# rb1_2_panelized.net
KiCad netlist of a schematic drawn in EAGLE
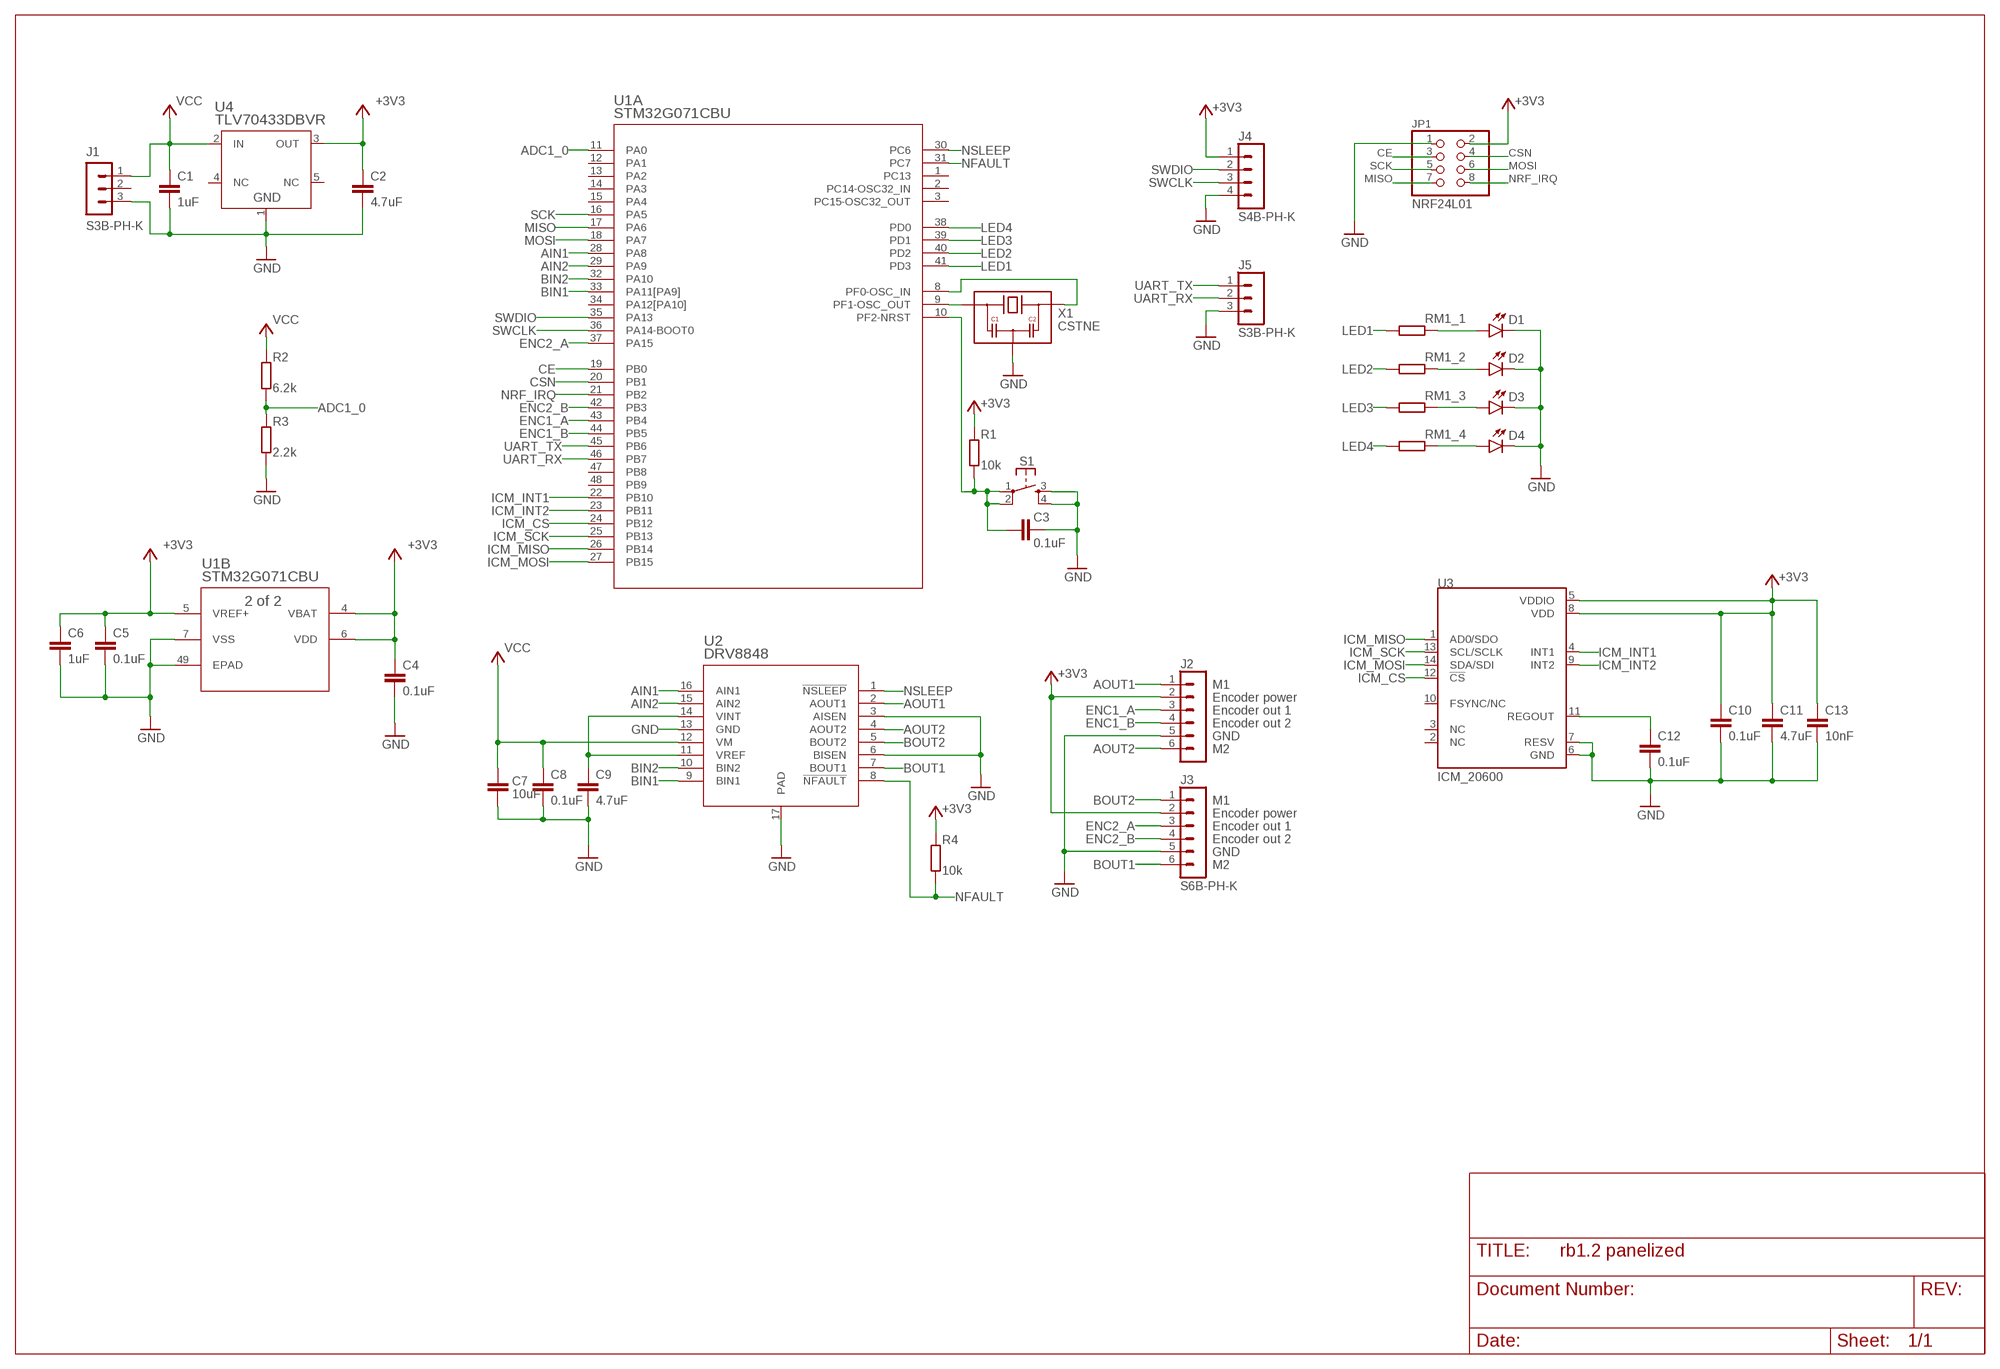
[diagram p0: schematic, sheet 1]

(export (version "E")
  (design (tool "Eeschema 10.0.6"))
  (components
    (comp (ref "C1")
      (value "1uF")
      (footprint "eagle-import:C0603K")
      (libsource (lib "eagle-import") (part "C-EU-K0603"))
    )
    (comp (ref "C2")
      (value "4.7uF")
      (footprint "eagle-import:C0603K")
      (libsource (lib "eagle-import") (part "C-EU-K0603"))
    )
    (comp (ref "C3")
      (value "0.1uF")
      (footprint "eagle-import:C0402K")
      (libsource (lib "eagle-import") (part "C-EU-K0402"))
    )
    (comp (ref "C4")
      (value "0.1uF")
      (footprint "eagle-import:C0603K")
      (libsource (lib "eagle-import") (part "C-EU-K0603"))
    )
    (comp (ref "C5")
      (value "0.1uF")
      (footprint "eagle-import:C0603K")
      (libsource (lib "eagle-import") (part "C-EU-K0603"))
    )
    (comp (ref "C6")
      (value "1uF")
      (footprint "eagle-import:C0603K")
      (libsource (lib "eagle-import") (part "C-EU-K0603"))
    )
    (comp (ref "C7")
      (value "10uF")
      (footprint "eagle-import:C1206K")
      (libsource (lib "eagle-import") (part "C-EU-K1206"))
    )
    (comp (ref "C8")
      (value "0.1uF")
      (footprint "eagle-import:C0603K")
      (libsource (lib "eagle-import") (part "C-EU-K0603"))
    )
    (comp (ref "C9")
      (value "4.7uF")
      (footprint "eagle-import:C0603K")
      (libsource (lib "eagle-import") (part "C-EU-K0603"))
    )
    (comp (ref "C10")
      (value "0.1uF")
      (footprint "eagle-import:C0603K")
      (libsource (lib "eagle-import") (part "C-EU-K0603"))
    )
    (comp (ref "C11")
      (value "4.7uF")
      (footprint "eagle-import:C0603K")
      (libsource (lib "eagle-import") (part "C-EU-K0603"))
    )
    (comp (ref "C12")
      (value "0.1uF")
      (footprint "eagle-import:C0603K")
      (libsource (lib "eagle-import") (part "C-EU-K0603"))
    )
    (comp (ref "C13")
      (value "10nF")
      (footprint "eagle-import:C0603K")
      (libsource (lib "eagle-import") (part "C-EU-K0603"))
    )
    (comp (ref "D1")
      (value "LED0805")
      (footprint "eagle-import:LED-0805")
      (libsource (lib "eagle-import") (part "LED0805"))
    )
    (comp (ref "D2")
      (value "LED0805")
      (footprint "eagle-import:LED-0805")
      (libsource (lib "eagle-import") (part "LED0805"))
    )
    (comp (ref "D3")
      (value "LED0805")
      (footprint "eagle-import:LED-0805")
      (libsource (lib "eagle-import") (part "LED0805"))
    )
    (comp (ref "D4")
      (value "LED0805")
      (footprint "eagle-import:LED-0805")
      (libsource (lib "eagle-import") (part "LED0805"))
    )
    (comp (ref "J1")
      (value "S3B-PH-K")
      (footprint "eagle-import:S3B-PH-K")
      (libsource (lib "eagle-import") (part "S3B-PH-K"))
    )
    (comp (ref "J2")
      (value "S6B-PH-K")
      (footprint "eagle-import:S6B-PH-K")
      (libsource (lib "eagle-import") (part "S6B-PH-K"))
    )
    (comp (ref "J3")
      (value "S6B-PH-K")
      (footprint "eagle-import:S6B-PH-K")
      (libsource (lib "eagle-import") (part "S6B-PH-K"))
    )
    (comp (ref "J4")
      (value "S4B-PH-K")
      (footprint "eagle-import:S4B-PH-K")
      (libsource (lib "eagle-import") (part "S4B-PH-K"))
    )
    (comp (ref "J5")
      (value "S3B-PH-K")
      (footprint "eagle-import:S3B-PH-K")
      (libsource (lib "eagle-import") (part "S3B-PH-K"))
    )
    (comp (ref "JP1")
      (value "NRF24L01")
      (footprint "eagle-import:2X04")
      (libsource (lib "eagle-import") (part "PINHD-2X4"))
    )
    (comp (ref "R1")
      (value "10k")
      (footprint "eagle-import:R0603")
      (libsource (lib "eagle-import") (part "R-EU0603"))
    )
    (comp (ref "R2")
      (value "6.2k")
      (footprint "eagle-import:R0603")
      (libsource (lib "eagle-import") (part "R-EU0603"))
    )
    (comp (ref "R3")
      (value "2.2k")
      (footprint "eagle-import:R0603")
      (libsource (lib "eagle-import") (part "R-EU0603"))
    )
    (comp (ref "R4")
      (value "10k")
      (footprint "eagle-import:R0603")
      (libsource (lib "eagle-import") (part "R-EU0603"))
    )
    (comp (ref "RM1")
      (value "RES_ARRAY")
      (footprint "eagle-import:0603-ARC")
      (libsource (lib "eagle-import") (part "RES_ARRAY"))
    )
    (comp (ref "S1")
      (value "MOMENTARY-SWITCH-SPST-2-[SMD-5.2MM]")
      (footprint "eagle-import:TACTILE_SWITCH_SMD_5.2MM")
      (libsource (lib "eagle-import") (part "MOMENTARY-SWITCH-SPST-2-[SMD-5.2MM]"))
    )
    (comp (ref "U1")
      (value "STM32G071CBU")
      (footprint "eagle-import:UFQFPN48-7X7MM")
      (libsource (lib "eagle-import") (part "STM32G0_UFQFPN48"))
    )
    (comp (ref "U2")
      (value "DRV8848")
      (footprint "eagle-import:HTSSOP")
      (libsource (lib "eagle-import") (part "DRV8848[NORMAL_PADS]"))
    )
    (comp (ref "U3")
      (value "ICM_20600")
      (footprint "eagle-import:14_PIN_LGA")
      (libsource (lib "eagle-import") (part "ICM_20600"))
    )
    (comp (ref "U4")
      (value "TLV70433DBVR")
      (footprint "eagle-import:SOT-23-5")
      (libsource (lib "eagle-import") (part "TLV70433DBVR[NORMAL_PADS]"))
    )
    (comp (ref "X1")
      (value "CSTNE")
      (footprint "eagle-import:MURATA_SMD_3P")
      (libsource (lib "eagle-import") (part "CSTNE"))
    )
  )
  (nets
    (net (code "1") (name "+3V3") (class "Default")
      (node (ref "C10") (pin "1") (pinfunction "1_1") (pintype "passive"))
      (node (ref "C11") (pin "1") (pinfunction "1_1") (pintype "passive"))
      (node (ref "C13") (pin "1") (pinfunction "1_1") (pintype "passive"))
      (node (ref "C2") (pin "1") (pinfunction "1_1") (pintype "passive"))
      (node (ref "C4") (pin "1") (pinfunction "1_1") (pintype "passive"))
      (node (ref "C5") (pin "1") (pinfunction "1_1") (pintype "passive"))
      (node (ref "C6") (pin "1") (pinfunction "1_1") (pintype "passive"))
      (node (ref "J2") (pin "2") (pinfunction "2_2") (pintype "passive"))
      (node (ref "J3") (pin "2") (pinfunction "2_2") (pintype "passive"))
      (node (ref "J4") (pin "1") (pinfunction "1_1") (pintype "passive"))
      (node (ref "JP1") (pin "2") (pinfunction "2_2") (pintype "passive"))
      (node (ref "R1") (pin "2") (pinfunction "2_2") (pintype "passive"))
      (node (ref "R4") (pin "2") (pinfunction "2_2") (pintype "passive"))
      (node (ref "U1") (pin "4") (pinfunction "VBAT_4") (pintype "power_in"))
      (node (ref "U1") (pin "5") (pinfunction "VREF+_5") (pintype "power_in"))
      (node (ref "U1") (pin "6") (pinfunction "VDD_6") (pintype "power_in"))
      (node (ref "U3") (pin "5") (pinfunction "VDDIO_5") (pintype "power_in"))
      (node (ref "U3") (pin "8") (pinfunction "VDD_8") (pintype "power_in"))
      (node (ref "U4") (pin "3") (pinfunction "OUT_3") (pintype "output"))
    )
    (net (code "2") (name "/ADC1_0") (class "Default")
      (node (ref "R2") (pin "1") (pinfunction "1_1") (pintype "passive"))
      (node (ref "R3") (pin "2") (pinfunction "2_2") (pintype "passive"))
      (node (ref "U1") (pin "11") (pinfunction "PA0_11") (pintype "bidirectional"))
    )
    (net (code "3") (name "/AIN1") (class "Default")
      (node (ref "U1") (pin "28") (pinfunction "PA8_28") (pintype "bidirectional"))
      (node (ref "U2") (pin "16") (pinfunction "AIN1_16") (pintype "input"))
    )
    (net (code "4") (name "/AIN2") (class "Default")
      (node (ref "U1") (pin "29") (pinfunction "PA9_29") (pintype "bidirectional"))
      (node (ref "U2") (pin "15") (pinfunction "AIN2_15") (pintype "input"))
    )
    (net (code "5") (name "/AOUT1") (class "Default")
      (node (ref "J2") (pin "1") (pinfunction "1_1") (pintype "passive"))
      (node (ref "U2") (pin "2") (pinfunction "AOUT1_2") (pintype "output"))
    )
    (net (code "6") (name "/AOUT2") (class "Default")
      (node (ref "J2") (pin "6") (pinfunction "6_6") (pintype "passive"))
      (node (ref "U2") (pin "4") (pinfunction "AOUT2_4") (pintype "output"))
    )
    (net (code "7") (name "/BIN1") (class "Default")
      (node (ref "U1") (pin "33") (pinfunction "PA11[PA9]_33") (pintype "bidirectional"))
      (node (ref "U2") (pin "9") (pinfunction "BIN1_9") (pintype "input"))
    )
    (net (code "8") (name "/BIN2") (class "Default")
      (node (ref "U1") (pin "32") (pinfunction "PA10_32") (pintype "bidirectional"))
      (node (ref "U2") (pin "10") (pinfunction "BIN2_10") (pintype "input"))
    )
    (net (code "9") (name "/BOUT1") (class "Default")
      (node (ref "J3") (pin "6") (pinfunction "6_6") (pintype "passive"))
      (node (ref "U2") (pin "7") (pinfunction "BOUT1_7") (pintype "output"))
    )
    (net (code "10") (name "/BOUT2") (class "Default")
      (node (ref "J3") (pin "1") (pinfunction "1_1") (pintype "passive"))
      (node (ref "U2") (pin "5") (pinfunction "BOUT2_5") (pintype "output"))
    )
    (net (code "11") (name "/CE") (class "Default")
      (node (ref "JP1") (pin "3") (pinfunction "3_3") (pintype "passive"))
      (node (ref "U1") (pin "19") (pinfunction "PB0_19") (pintype "bidirectional"))
    )
    (net (code "12") (name "/CSN") (class "Default")
      (node (ref "JP1") (pin "4") (pinfunction "4_4") (pintype "passive"))
      (node (ref "U1") (pin "20") (pinfunction "PB1_20") (pintype "bidirectional"))
    )
    (net (code "13") (name "/ENC1_A") (class "Default")
      (node (ref "J2") (pin "3") (pinfunction "3_3") (pintype "passive"))
      (node (ref "U1") (pin "43") (pinfunction "PB4_43") (pintype "bidirectional"))
    )
    (net (code "14") (name "/ENC1_B") (class "Default")
      (node (ref "J2") (pin "4") (pinfunction "4_4") (pintype "passive"))
      (node (ref "U1") (pin "44") (pinfunction "PB5_44") (pintype "bidirectional"))
    )
    (net (code "15") (name "/ENC2_A") (class "Default")
      (node (ref "J3") (pin "3") (pinfunction "3_3") (pintype "passive"))
      (node (ref "U1") (pin "37") (pinfunction "PA15_37") (pintype "bidirectional"))
    )
    (net (code "16") (name "/ENC2_B") (class "Default")
      (node (ref "J3") (pin "4") (pinfunction "4_4") (pintype "passive"))
      (node (ref "U1") (pin "42") (pinfunction "PB3_42") (pintype "bidirectional"))
    )
    (net (code "17") (name "/ICM_CS") (class "Default")
      (node (ref "U1") (pin "24") (pinfunction "PB12_24") (pintype "bidirectional"))
      (node (ref "U3") (pin "12") (pinfunction "~{CS}_12") (pintype "input"))
    )
    (net (code "18") (name "/ICM_INT1") (class "Default")
      (node (ref "U1") (pin "22") (pinfunction "PB10_22") (pintype "bidirectional"))
      (node (ref "U3") (pin "4") (pinfunction "INT1_4") (pintype "output"))
    )
    (net (code "19") (name "/ICM_INT2") (class "Default")
      (node (ref "U1") (pin "23") (pinfunction "PB11_23") (pintype "bidirectional"))
      (node (ref "U3") (pin "9") (pinfunction "INT2_9") (pintype "output"))
    )
    (net (code "20") (name "/ICM_MISO") (class "Default")
      (node (ref "U1") (pin "26") (pinfunction "PB14_26") (pintype "bidirectional"))
      (node (ref "U3") (pin "1") (pinfunction "AD0/SDO_1") (pintype "output"))
    )
    (net (code "21") (name "/ICM_MOSI") (class "Default")
      (node (ref "U1") (pin "27") (pinfunction "PB15_27") (pintype "bidirectional"))
      (node (ref "U3") (pin "14") (pinfunction "SDA/SDI_14") (pintype "bidirectional"))
    )
    (net (code "22") (name "/ICM_SCK") (class "Default")
      (node (ref "U1") (pin "25") (pinfunction "PB13_25") (pintype "bidirectional"))
      (node (ref "U3") (pin "13") (pinfunction "SCL/SCLK_13") (pintype "bidirectional"))
    )
    (net (code "23") (name "/LED1") (class "Default")
      (node (ref "RM1") (pin "1") (pinfunction "1_1") (pintype "passive"))
      (node (ref "U1") (pin "41") (pinfunction "PD3_41") (pintype "bidirectional"))
    )
    (net (code "24") (name "/LED2") (class "Default")
      (node (ref "RM1") (pin "2") (pinfunction "1_2") (pintype "passive"))
      (node (ref "U1") (pin "40") (pinfunction "PD2_40") (pintype "bidirectional"))
    )
    (net (code "25") (name "/LED3") (class "Default")
      (node (ref "RM1") (pin "3") (pinfunction "1_3") (pintype "passive"))
      (node (ref "U1") (pin "39") (pinfunction "PD1_39") (pintype "bidirectional"))
    )
    (net (code "26") (name "/LED4") (class "Default")
      (node (ref "RM1") (pin "4") (pinfunction "1_4") (pintype "passive"))
      (node (ref "U1") (pin "38") (pinfunction "PD0_38") (pintype "bidirectional"))
    )
    (net (code "27") (name "/MISO") (class "Default")
      (node (ref "JP1") (pin "7") (pinfunction "7_7") (pintype "passive"))
      (node (ref "U1") (pin "17") (pinfunction "PA6_17") (pintype "bidirectional"))
    )
    (net (code "28") (name "/MOSI") (class "Default")
      (node (ref "JP1") (pin "6") (pinfunction "6_6") (pintype "passive"))
      (node (ref "U1") (pin "18") (pinfunction "PA7_18") (pintype "bidirectional"))
    )
    (net (code "29") (name "/NFAULT") (class "Default")
      (node (ref "R4") (pin "1") (pinfunction "1_1") (pintype "passive"))
      (node (ref "U1") (pin "31") (pinfunction "PC7_31") (pintype "bidirectional"))
      (node (ref "U2") (pin "8") (pinfunction "~{NFAULT}_8") (pintype "output"))
    )
    (net (code "30") (name "/NRF_IRQ") (class "Default")
      (node (ref "JP1") (pin "8") (pinfunction "8_8") (pintype "passive"))
      (node (ref "U1") (pin "21") (pinfunction "PB2_21") (pintype "bidirectional"))
    )
    (net (code "31") (name "/NSLEEP") (class "Default")
      (node (ref "U1") (pin "30") (pinfunction "PC6_30") (pintype "bidirectional"))
      (node (ref "U2") (pin "1") (pinfunction "~{NSLEEP}_1") (pintype "input"))
    )
    (net (code "32") (name "/SCK") (class "Default")
      (node (ref "JP1") (pin "5") (pinfunction "5_5") (pintype "passive"))
      (node (ref "U1") (pin "16") (pinfunction "PA5_16") (pintype "bidirectional"))
    )
    (net (code "33") (name "/SWCLK") (class "Default")
      (node (ref "J4") (pin "3") (pinfunction "3_3") (pintype "passive"))
      (node (ref "U1") (pin "36") (pinfunction "PA14-BOOT0_36") (pintype "bidirectional"))
    )
    (net (code "34") (name "/SWDIO") (class "Default")
      (node (ref "J4") (pin "2") (pinfunction "2_2") (pintype "passive"))
      (node (ref "U1") (pin "35") (pinfunction "PA13_35") (pintype "bidirectional"))
    )
    (net (code "35") (name "/UART_RX") (class "Default")
      (node (ref "J5") (pin "2") (pinfunction "2_2") (pintype "passive"))
      (node (ref "U1") (pin "46") (pinfunction "PB7_46") (pintype "bidirectional"))
    )
    (net (code "36") (name "/UART_TX") (class "Default")
      (node (ref "J5") (pin "1") (pinfunction "1_1") (pintype "passive"))
      (node (ref "U1") (pin "45") (pinfunction "PB6_45") (pintype "bidirectional"))
    )
    (net (code "37") (name "GND") (class "Default")
      (node (ref "C1") (pin "2") (pinfunction "2_2") (pintype "passive"))
      (node (ref "C10") (pin "2") (pinfunction "2_2") (pintype "passive"))
      (node (ref "C11") (pin "2") (pinfunction "2_2") (pintype "passive"))
      (node (ref "C12") (pin "2") (pinfunction "2_2") (pintype "passive"))
      (node (ref "C13") (pin "2") (pinfunction "2_2") (pintype "passive"))
      (node (ref "C2") (pin "2") (pinfunction "2_2") (pintype "passive"))
      (node (ref "C3") (pin "1") (pinfunction "1_1") (pintype "passive"))
      (node (ref "C4") (pin "2") (pinfunction "2_2") (pintype "passive"))
      (node (ref "C5") (pin "2") (pinfunction "2_2") (pintype "passive"))
      (node (ref "C6") (pin "2") (pinfunction "2_2") (pintype "passive"))
      (node (ref "C7") (pin "2") (pinfunction "2_2") (pintype "passive"))
      (node (ref "C8") (pin "2") (pinfunction "2_2") (pintype "passive"))
      (node (ref "C9") (pin "2") (pinfunction "2_2") (pintype "passive"))
      (node (ref "D1") (pin "-") (pinfunction "C_-") (pintype "passive"))
      (node (ref "D2") (pin "-") (pinfunction "C_-") (pintype "passive"))
      (node (ref "D3") (pin "-") (pinfunction "C_-") (pintype "passive"))
      (node (ref "D4") (pin "-") (pinfunction "C_-") (pintype "passive"))
      (node (ref "J1") (pin "3") (pinfunction "3_3") (pintype "passive"))
      (node (ref "J2") (pin "5") (pinfunction "5_5") (pintype "passive"))
      (node (ref "J3") (pin "5") (pinfunction "5_5") (pintype "passive"))
      (node (ref "J4") (pin "4") (pinfunction "4_4") (pintype "passive"))
      (node (ref "J5") (pin "3") (pinfunction "3_3") (pintype "passive"))
      (node (ref "JP1") (pin "1") (pinfunction "1_1") (pintype "passive"))
      (node (ref "R3") (pin "1") (pinfunction "1_1") (pintype "passive"))
      (node (ref "S1") (pin "3") (pinfunction "3_3") (pintype "passive"))
      (node (ref "S1") (pin "4") (pinfunction "4_4") (pintype "passive"))
      (node (ref "U1") (pin "49") (pinfunction "EPAD_49") (pintype "passive"))
      (node (ref "U1") (pin "7") (pinfunction "VSS_7") (pintype "power_in"))
      (node (ref "U2") (pin "13") (pinfunction "GND_13") (pintype "power_in"))
      (node (ref "U2") (pin "17") (pinfunction "PAD_17") (pintype "passive"))
      (node (ref "U2") (pin "3") (pinfunction "AISEN_3") (pintype "output"))
      (node (ref "U2") (pin "6") (pinfunction "BISEN_6") (pintype "output"))
      (node (ref "U3") (pin "6") (pinfunction "GND_6") (pintype "power_in"))
      (node (ref "U3") (pin "7") (pinfunction "RESV_7") (pintype "power_in"))
      (node (ref "U4") (pin "1") (pinfunction "GND_1") (pintype "power_in"))
      (node (ref "X1") (pin "2") (pinfunction "GND_2") (pintype "passive"))
    )
    (net (code "38") (name "Net-(D1-A)") (class "Default")
      (node (ref "D1") (pin "+") (pinfunction "A_+") (pintype "passive"))
      (node (ref "RM1") (pin "8") (pinfunction "2_8") (pintype "passive"))
    )
    (net (code "39") (name "Net-(D2-A)") (class "Default")
      (node (ref "D2") (pin "+") (pinfunction "A_+") (pintype "passive"))
      (node (ref "RM1") (pin "7") (pinfunction "2_7") (pintype "passive"))
    )
    (net (code "40") (name "Net-(D3-A)") (class "Default")
      (node (ref "D3") (pin "+") (pinfunction "A_+") (pintype "passive"))
      (node (ref "RM1") (pin "6") (pinfunction "2_6") (pintype "passive"))
    )
    (net (code "41") (name "Net-(D4-A)") (class "Default")
      (node (ref "D4") (pin "+") (pinfunction "A_+") (pintype "passive"))
      (node (ref "RM1") (pin "5") (pinfunction "2_5") (pintype "passive"))
    )
    (net (code "42") (name "Net-(U1A-PF0-OSC_IN)") (class "Default")
      (node (ref "U1") (pin "8") (pinfunction "PF0-OSC_IN_8") (pintype "bidirectional"))
      (node (ref "X1") (pin "3") (pinfunction "OUT_3") (pintype "passive"))
    )
    (net (code "43") (name "Net-(U1A-PF1-OSC_OUT)") (class "Default")
      (node (ref "U1") (pin "9") (pinfunction "PF1-OSC_OUT_9") (pintype "bidirectional"))
      (node (ref "X1") (pin "1") (pinfunction "IN_1") (pintype "passive"))
    )
    (net (code "44") (name "Net-(U1A-PF2-NRST)") (class "Default")
      (node (ref "C3") (pin "2") (pinfunction "2_2") (pintype "passive"))
      (node (ref "R1") (pin "1") (pinfunction "1_1") (pintype "passive"))
      (node (ref "S1") (pin "1") (pinfunction "1_1") (pintype "passive"))
      (node (ref "S1") (pin "2") (pinfunction "2_2") (pintype "passive"))
      (node (ref "U1") (pin "10") (pinfunction "PF2-NRST_10") (pintype "bidirectional"))
    )
    (net (code "45") (name "Net-(U2-VINT)") (class "Default")
      (node (ref "C9") (pin "1") (pinfunction "1_1") (pintype "passive"))
      (node (ref "U2") (pin "11") (pinfunction "VREF_11") (pintype "input"))
      (node (ref "U2") (pin "14") (pinfunction "VINT_14") (pintype "input"))
    )
    (net (code "46") (name "Net-(U3-REGOUT)") (class "Default")
      (node (ref "C12") (pin "1") (pinfunction "1_1") (pintype "passive"))
      (node (ref "U3") (pin "11") (pinfunction "REGOUT_11") (pintype "passive"))
    )
    (net (code "47") (name "VCC") (class "Default")
      (node (ref "C1") (pin "1") (pinfunction "1_1") (pintype "passive"))
      (node (ref "C7") (pin "1") (pinfunction "1_1") (pintype "passive"))
      (node (ref "C8") (pin "1") (pinfunction "1_1") (pintype "passive"))
      (node (ref "J1") (pin "1") (pinfunction "1_1") (pintype "passive"))
      (node (ref "R2") (pin "2") (pinfunction "2_2") (pintype "passive"))
      (node (ref "U2") (pin "12") (pinfunction "VM_12") (pintype "power_in"))
      (node (ref "U4") (pin "2") (pinfunction "IN_2") (pintype "input"))
    )
    (net (code "48") (name "unconnected-(J1-Pad2)") (class "Default")
      (node (ref "J1") (pin "2") (pinfunction "2_2") (pintype "passive"))
    )
    (net (code "49") (name "unconnected-(U1A-PA1-Pad12)") (class "Default")
      (node (ref "U1") (pin "12") (pinfunction "PA1_12") (pintype "bidirectional"))
    )
    (net (code "50") (name "unconnected-(U1A-PA2-Pad13)") (class "Default")
      (node (ref "U1") (pin "13") (pinfunction "PA2_13") (pintype "bidirectional"))
    )
    (net (code "51") (name "unconnected-(U1A-PA3-Pad14)") (class "Default")
      (node (ref "U1") (pin "14") (pinfunction "PA3_14") (pintype "bidirectional"))
    )
    (net (code "52") (name "unconnected-(U1A-PA4-Pad15)") (class "Default")
      (node (ref "U1") (pin "15") (pinfunction "PA4_15") (pintype "bidirectional"))
    )
    (net (code "53") (name "unconnected-(U1A-PA12[PA10]-Pad34)") (class "Default")
      (node (ref "U1") (pin "34") (pinfunction "PA12[PA10]_34") (pintype "bidirectional"))
    )
    (net (code "54") (name "unconnected-(U1A-PB8-Pad47)") (class "Default")
      (node (ref "U1") (pin "47") (pinfunction "PB8_47") (pintype "bidirectional"))
    )
    (net (code "55") (name "unconnected-(U1A-PB9-Pad48)") (class "Default")
      (node (ref "U1") (pin "48") (pinfunction "PB9_48") (pintype "bidirectional"))
    )
    (net (code "56") (name "unconnected-(U1A-PC13-Pad1)") (class "Default")
      (node (ref "U1") (pin "1") (pinfunction "PC13_1") (pintype "bidirectional"))
    )
    (net (code "57") (name "unconnected-(U1A-PC14-OSC32_IN-Pad2)") (class "Default")
      (node (ref "U1") (pin "2") (pinfunction "PC14-OSC32_IN_2") (pintype "bidirectional"))
    )
    (net (code "58") (name "unconnected-(U1A-PC15-OSC32_OUT-Pad3)") (class "Default")
      (node (ref "U1") (pin "3") (pinfunction "PC15-OSC32_OUT_3") (pintype "bidirectional"))
    )
    (net (code "59") (name "unconnected-(U3-FSYNC{slash}NC-Pad10)") (class "Default")
      (node (ref "U3") (pin "10") (pinfunction "FSYNC/NC_10") (pintype "input"))
    )
    (net (code "60") (name "unconnected-(U3-NC-Pad2)") (class "Default")
      (node (ref "U3") (pin "2") (pinfunction "NC_2") (pintype "no_connect"))
    )
    (net (code "61") (name "unconnected-(U3-NC-Pad3)") (class "Default")
      (node (ref "U3") (pin "3") (pinfunction "NC_3") (pintype "no_connect"))
    )
    (net (code "62") (name "unconnected-(U4-NC-Pad4)") (class "Default")
      (node (ref "U4") (pin "4") (pinfunction "NC_4") (pintype "no_connect"))
    )
    (net (code "63") (name "unconnected-(U4-NC-Pad5)") (class "Default")
      (node (ref "U4") (pin "5") (pinfunction "NC_5") (pintype "no_connect"))
    )
  )
)
